# RPL_IGNITION.net
KiCad netlist of a schematic drawn in Altium Designer
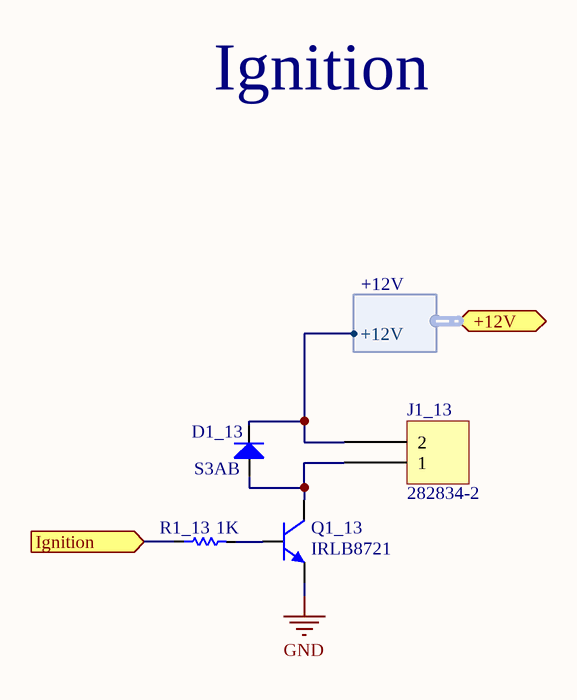
[diagram p0: RPL_IGNITION.SchDoc]

(export (version "E")
  (design (tool "Eeschema 10.0.6"))
  (components
    (comp (ref "D1_13")
      (value "S3AB")
      (footprint "S3AB")
      (libsource (lib "Generic_Library") (part "Diod Rectifire"))
    )
    (comp (ref "J1_13")
      (value "282834-2")
      (footprint "TE 282834-2")
      (description "TERM BLOCK 2POS SIDE ENT 2.54MM")
      (fields (field (name "MANUFACTURER") "TE Connectivity AMP Connectors") (field (name "VOLTAGE") "150V"))
      (libsource (lib "Celestial Library Database") (part "2 Pin"))
    )
    (comp (ref "Q1_13")
      (value "IRLB8721")
      (footprint "TO220")
      (description "NPN General Purpose Amplifier")
      (libsource (lib "Generic_Library") (part "IRLB8721"))
    )
    (comp (ref "R1_13")
      (value "1K")
      (footprint "SMD Resistors:RES 0805")
      (fields (field (name "Comment") "Res"))
      (libsource (lib "Generic_Library") (part "Res"))
    )
  )
  (nets
    (net (code "2") (name "/Ignition") (class "Default")
      (node (ref "R1_13") (pin "1") (pinfunction "1_1") (pintype "passive"))
    )
    (net (code "4") (name "GND") (class "Default")
      (node (ref "Q1_13") (pin "1") (pinfunction "E_1") (pintype "passive"))
    )
    (net (code "5") (name "Net-(D1_13-PadK)") (class "Default")
      (node (ref "D1_13") (pin "K") (pinfunction "K_K") (pintype "passive"))
      (node (ref "J1_13") (pin "2") (pinfunction "2_2") (pintype "passive"))
    )
    (net (code "6") (name "Net-(Q1_13-B)") (class "Default")
      (node (ref "Q1_13") (pin "2") (pinfunction "B_2") (pintype "passive"))
      (node (ref "R1_13") (pin "2") (pinfunction "2_2") (pintype "passive"))
    )
    (net (code "7") (name "Net-(Q1_13-C)") (class "Default")
      (node (ref "D1_13") (pin "A") (pinfunction "A_A") (pintype "passive"))
      (node (ref "J1_13") (pin "1") (pinfunction "1_1") (pintype "passive"))
      (node (ref "Q1_13") (pin "3") (pinfunction "C_3") (pintype "passive"))
    )
  )
)
